# PAGE4_-_SENSORS.net
KiCad netlist of a schematic drawn in Altium Designer
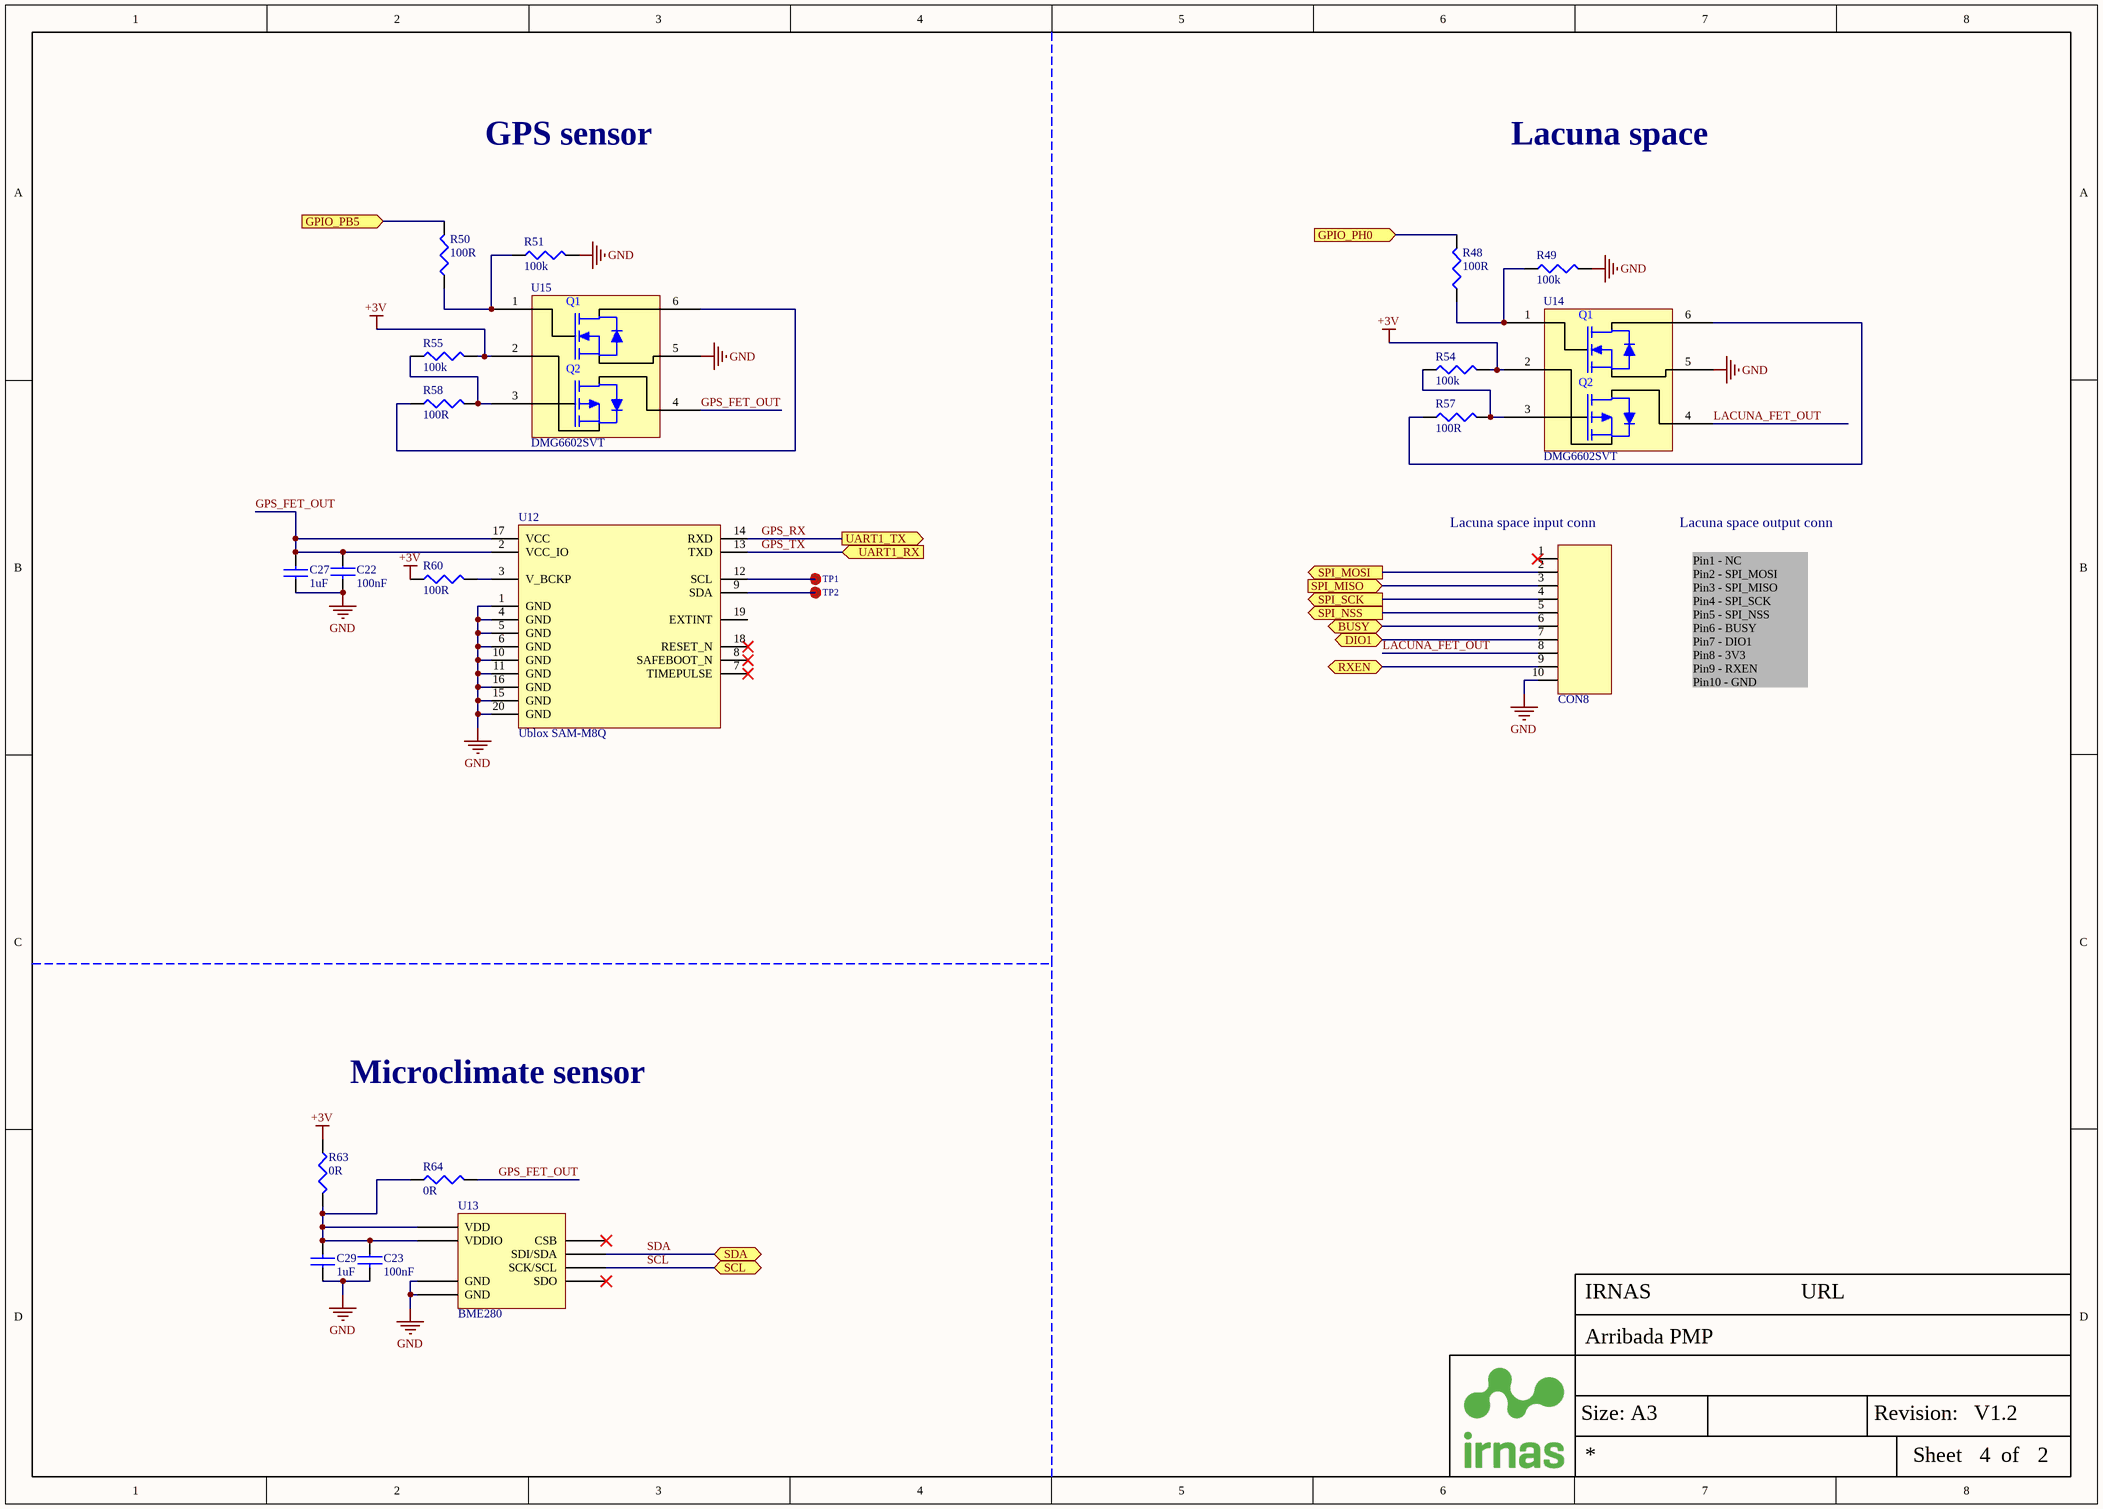
[diagram p0: PAGE4 - SENSORS.SchDoc]

(export (version "E")
  (design (tool "Eeschema 10.0.6"))
  (components
    (comp (ref "C22")
      (value "100nF")
      (footprint "CAP0603")
      (description "MURATA - GRM188R71C104KA01J - CAP, MLCC, X7R, 0.1UF, 16V, 0603")
      (fields
        (field (name "MANUFACTURER") "MURATA")
        (field (name "MANUFACTURER PART NUMBER") "GRM188R71C104KA01J")
      )
      (libsource (lib "Passive") (part "C - 100nF"))
    )
    (comp (ref "C23")
      (value "100nF")
      (footprint "CAP0603")
      (description "MURATA - GRM188R71C104KA01J - CAP, MLCC, X7R, 0.1UF, 16V, 0603")
      (fields
        (field (name "MANUFACTURER") "MURATA")
        (field (name "MANUFACTURER PART NUMBER") "GRM188R71C104KA01J")
      )
      (libsource (lib "Passive") (part "C - 100nF"))
    )
    (comp (ref "C27")
      (value "1uF")
      (footprint "CAP0603")
      (description "MURATA - GRM188R61H105KAALD - CAP, MLCC, X5R, 1UF, 50V, 0603")
      (fields
        (field (name "MANUFACTURER") "MURATA")
        (field (name "MANUFACTURER PART NUMBER") "GRM188R61H105KAALD")
      )
      (libsource (lib "Passive") (part "C - 1uF"))
    )
    (comp (ref "C29")
      (value "1uF")
      (footprint "CAP0603")
      (description "MURATA - GRM188R61H105KAALD - CAP, MLCC, X5R, 1UF, 50V, 0603")
      (fields
        (field (name "MANUFACTURER") "MURATA")
        (field (name "MANUFACTURER PART NUMBER") "GRM188R61H105KAALD")
      )
      (libsource (lib "Passive") (part "C - 1uF"))
    )
    (comp (ref "CON8")
      (value "53261-1071")
      (footprint "PICOBLADE 10PIN")
      (description "Wire-To-Board Connector, Right Angle, 1.25 mm, 10 Contacts, Header, PicoBlade 53261 Series")
      (libsource (lib "Connectors") (part "PicoBlade 10pin"))
    )
    (comp (ref "R48")
      (value "100R")
      (footprint "RES0603")
      (description "MULTICOMP - MC0063W06031100R - RES, THICK FILM, 100R, 1%, 0.063W, 0603")
      (fields
        (field (name "MANUFACTURER") "MULTICOMP")
        (field (name "MANUFACTURER PART NUMBER") "MC0063W06031100R")
      )
      (libsource (lib "Passive") (part "R - 100R"))
    )
    (comp (ref "R49")
      (value "100k")
      (footprint "RES0603")
      (description "MULTICOMP - MCMR06X104 JTL - RES, CERAMIC, 100K, 5%, 0.1W, 0603")
      (fields
        (field (name "MANUFACTURER") "MULTICOMP")
        (field (name "MANUFACTURER PART NUMBER") "MCMR06X104 JTL")
      )
      (libsource (lib "Passive") (part "R - 100k"))
    )
    (comp (ref "R50")
      (value "100R")
      (footprint "RES0603")
      (description "MULTICOMP - MC0063W06031100R - RES, THICK FILM, 100R, 1%, 0.063W, 0603")
      (fields
        (field (name "MANUFACTURER") "MULTICOMP")
        (field (name "MANUFACTURER PART NUMBER") "MC0063W06031100R")
      )
      (libsource (lib "Passive") (part "R - 100R"))
    )
    (comp (ref "R51")
      (value "100k")
      (footprint "RES0603")
      (description "MULTICOMP - MCMR06X104 JTL - RES, CERAMIC, 100K, 5%, 0.1W, 0603")
      (fields
        (field (name "MANUFACTURER") "MULTICOMP")
        (field (name "MANUFACTURER PART NUMBER") "MCMR06X104 JTL")
      )
      (libsource (lib "Passive") (part "R - 100k"))
    )
    (comp (ref "R54")
      (value "100k")
      (footprint "RES0603")
      (description "MULTICOMP - MCMR06X104 JTL - RES, CERAMIC, 100K, 5%, 0.1W, 0603")
      (fields
        (field (name "MANUFACTURER") "MULTICOMP")
        (field (name "MANUFACTURER PART NUMBER") "MCMR06X104 JTL")
      )
      (libsource (lib "Passive") (part "R - 100k"))
    )
    (comp (ref "R55")
      (value "100k")
      (footprint "RES0603")
      (description "MULTICOMP - MCMR06X104 JTL - RES, CERAMIC, 100K, 5%, 0.1W, 0603")
      (fields
        (field (name "MANUFACTURER") "MULTICOMP")
        (field (name "MANUFACTURER PART NUMBER") "MCMR06X104 JTL")
      )
      (libsource (lib "Passive") (part "R - 100k"))
    )
    (comp (ref "R57")
      (value "100R")
      (footprint "RES0603")
      (description "MULTICOMP - MC0063W06031100R - RES, THICK FILM, 100R, 1%, 0.063W, 0603")
      (fields
        (field (name "MANUFACTURER") "MULTICOMP")
        (field (name "MANUFACTURER PART NUMBER") "MC0063W06031100R")
      )
      (libsource (lib "Passive") (part "R - 100R"))
    )
    (comp (ref "R58")
      (value "100R")
      (footprint "RES0603")
      (description "MULTICOMP - MC0063W06031100R - RES, THICK FILM, 100R, 1%, 0.063W, 0603")
      (fields
        (field (name "MANUFACTURER") "MULTICOMP")
        (field (name "MANUFACTURER PART NUMBER") "MC0063W06031100R")
      )
      (libsource (lib "Passive") (part "R - 100R"))
    )
    (comp (ref "R60")
      (value "100R")
      (footprint "RES0603")
      (description "MULTICOMP - MC0063W06031100R - RES, THICK FILM, 100R, 1%, 0.063W, 0603")
      (fields
        (field (name "MANUFACTURER") "MULTICOMP")
        (field (name "MANUFACTURER PART NUMBER") "MC0063W06031100R")
      )
      (libsource (lib "Passive") (part "R - 100R"))
    )
    (comp (ref "R63")
      (value "0R")
      (footprint "RES0603")
      (description "BOURNS - CR0603-J/-000ELF - RES, THICK FILM, 0R, 5%, 0.1W, 0603")
      (fields
        (field (name "MANUFACTURER") "BOURNS")
        (field (name "MANUFACTURER PART NUMBER") "CR0603-J/-000ELF")
      )
      (libsource (lib "Passive") (part "R - 0R"))
    )
    (comp (ref "R64")
      (value "0R")
      (footprint "RES0603")
      (description "BOURNS - CR0603-J/-000ELF - RES, THICK FILM, 0R, 5%, 0.1W, 0603")
      (fields
        (field (name "MANUFACTURER") "BOURNS")
        (field (name "MANUFACTURER PART NUMBER") "CR0603-J/-000ELF")
      )
      (libsource (lib "Passive") (part "R - 0R"))
    )
    (comp (ref "TP1")
      (value "TestPoint")
      (footprint "Passive:TestPoint:1.2x1.2mm")
      (description "TEST POINT ROUND SMD")
      (libsource (lib "Passive") (part "TestPoint"))
    )
    (comp (ref "TP2")
      (value "TestPoint")
      (footprint "Passive:TestPoint:1.2x1.2mm")
      (description "TEST POINT ROUND SMD")
      (libsource (lib "Passive") (part "TestPoint"))
    )
    (comp (ref "U12")
      (value "Ublox SAM-M8Q")
      (footprint "SAM-M8Q")
      (description "SAM-M8 RF Receiver BeiDou, Galileo, GLONASS, GNSS, GPS -160dBm")
      (fields (field (name "MANUFACTURER") "u-blox") (field (name "MANUFACTURER PART NUMBER") "MAX-M8Q-0"))
      (libsource (lib "Active") (part "RF - UBLOX-SAM-M8Q"))
    )
    (comp (ref "U13")
      (value "BME280")
      (footprint "BME280")
      (description "Humidity Temperature Sensor 0 ~ 100% RH I²C, SPI ±3% 1s Surface Mount")
      (libsource (lib "Active") (part "SEN - BME280"))
    )
    (comp (ref "U14")
      (value "DMG6602SVT")
      (footprint "TSOT26")
      (description "Dual MOSFET, N and P Channel, 3.4 A, 30 V, 0.038 ohm, 10 V, 1 V")
      (libsource (lib "Active") (part "T_M - DMG6602SVT"))
    )
    (comp (ref "U15")
      (value "DMG6602SVT")
      (footprint "TSOT26")
      (description "Dual MOSFET, N and P Channel, 3.4 A, 30 V, 0.038 ohm, 10 V, 1 V")
      (libsource (lib "Active") (part "T_M - DMG6602SVT"))
    )
  )
  (nets
    (net (code "1") (name "+3V") (class "Default")
      (node (ref "R54") (pin "2") (pinfunction "2_2") (pintype "passive"))
      (node (ref "R55") (pin "2") (pinfunction "2_2") (pintype "passive"))
      (node (ref "R60") (pin "1") (pinfunction "1_1") (pintype "passive"))
      (node (ref "R63") (pin "1") (pinfunction "1_1") (pintype "passive"))
      (node (ref "U14") (pin "2") (pinfunction "S2_2") (pintype "open_collector"))
      (node (ref "U15") (pin "2") (pinfunction "S2_2") (pintype "open_collector"))
    )
    (net (code "2") (name "/BUSY") (class "Default")
      (node (ref "CON8") (pin "6") (pinfunction "6_6") (pintype "passive"))
    )
    (net (code "3") (name "/DIO1") (class "Default")
      (node (ref "CON8") (pin "7") (pinfunction "7_7") (pintype "passive"))
    )
    (net (code "4") (name "/GPIO_PB5") (class "Default")
      (node (ref "R50") (pin "2") (pinfunction "2_2") (pintype "passive"))
    )
    (net (code "5") (name "/GPIO_PH0") (class "Default")
      (node (ref "R48") (pin "2") (pinfunction "2_2") (pintype "passive"))
    )
    (net (code "6") (name "/GPS_FET_OUT") (class "Default")
      (node (ref "C22") (pin "1") (pinfunction "1_1") (pintype "passive"))
      (node (ref "C27") (pin "2") (pinfunction "2_2") (pintype "passive"))
      (node (ref "R64") (pin "2") (pinfunction "2_2") (pintype "passive"))
      (node (ref "U12") (pin "17") (pinfunction "VCC_17") (pintype "passive"))
      (node (ref "U12") (pin "2") (pinfunction "VCC_IO_2") (pintype "passive"))
      (node (ref "U15") (pin "4") (pinfunction "D2_4") (pintype "open_collector"))
    )
    (net (code "7") (name "/GPS_RX") (class "Default")
      (node (ref "U12") (pin "14") (pinfunction "RXD_14") (pintype "passive"))
    )
    (net (code "8") (name "/GPS_TX") (class "Default")
      (node (ref "U12") (pin "13") (pinfunction "TXD_13") (pintype "passive"))
    )
    (net (code "9") (name "/LACUNA_FET_OUT") (class "Default")
      (node (ref "CON8") (pin "8") (pinfunction "8_8") (pintype "passive"))
      (node (ref "U14") (pin "4") (pinfunction "D2_4") (pintype "open_collector"))
    )
    (net (code "10") (name "/RXEN") (class "Default")
      (node (ref "CON8") (pin "9") (pinfunction "9_9") (pintype "passive"))
    )
    (net (code "11") (name "/SCL") (class "Default")
      (node (ref "U13") (pin "4") (pinfunction "SCK/SCL_4") (pintype "passive"))
    )
    (net (code "12") (name "/SDA") (class "Default")
      (node (ref "U13") (pin "3") (pinfunction "SDI/SDA_3") (pintype "passive"))
    )
    (net (code "13") (name "/SPI_MISO") (class "Default")
      (node (ref "CON8") (pin "3") (pinfunction "3_3") (pintype "passive"))
    )
    (net (code "14") (name "/SPI_MOSI") (class "Default")
      (node (ref "CON8") (pin "2") (pinfunction "2_2") (pintype "passive"))
    )
    (net (code "15") (name "/SPI_NSS") (class "Default")
      (node (ref "CON8") (pin "5") (pinfunction "5_5") (pintype "passive"))
    )
    (net (code "16") (name "/SPI_SCK") (class "Default")
      (node (ref "CON8") (pin "4") (pinfunction "4_4") (pintype "passive"))
    )
    (net (code "17") (name "GND") (class "Default")
      (node (ref "C22") (pin "2") (pinfunction "2_2") (pintype "passive"))
      (node (ref "C23") (pin "2") (pinfunction "2_2") (pintype "passive"))
      (node (ref "C27") (pin "1") (pinfunction "1_1") (pintype "passive"))
      (node (ref "C29") (pin "1") (pinfunction "1_1") (pintype "passive"))
      (node (ref "CON8") (pin "10") (pinfunction "10_10") (pintype "passive"))
      (node (ref "R49") (pin "2") (pinfunction "2_2") (pintype "passive"))
      (node (ref "R51") (pin "2") (pinfunction "2_2") (pintype "passive"))
      (node (ref "U12") (pin "1") (pinfunction "GND_1") (pintype "passive"))
      (node (ref "U12") (pin "10") (pinfunction "GND_10") (pintype "passive"))
      (node (ref "U12") (pin "11") (pinfunction "GND_11") (pintype "passive"))
      (node (ref "U12") (pin "15") (pinfunction "GND_15") (pintype "passive"))
      (node (ref "U12") (pin "16") (pinfunction "GND_16") (pintype "passive"))
      (node (ref "U12") (pin "20") (pinfunction "GND_20") (pintype "passive"))
      (node (ref "U12") (pin "4") (pinfunction "GND_4") (pintype "passive"))
      (node (ref "U12") (pin "5") (pinfunction "GND_5") (pintype "passive"))
      (node (ref "U12") (pin "6") (pinfunction "GND_6") (pintype "passive"))
      (node (ref "U13") (pin "1") (pinfunction "GND_1") (pintype "passive"))
      (node (ref "U13") (pin "7") (pinfunction "GND_7") (pintype "passive"))
      (node (ref "U14") (pin "5") (pinfunction "S1_5") (pintype "open_collector"))
      (node (ref "U15") (pin "5") (pinfunction "S1_5") (pintype "open_collector"))
    )
    (net (code "18") (name "Net-(U12-SCL)") (class "Default")
      (node (ref "TP1") (pin "0") (pinfunction "0_0") (pintype "passive"))
      (node (ref "U12") (pin "12") (pinfunction "SCL_12") (pintype "passive"))
    )
    (net (code "19") (name "Net-(U12-SDA)") (class "Default")
      (node (ref "TP2") (pin "0") (pinfunction "0_0") (pintype "passive"))
      (node (ref "U12") (pin "9") (pinfunction "SDA_9") (pintype "passive"))
    )
    (net (code "20") (name "Net-(U12-V_BCKP)") (class "Default")
      (node (ref "R60") (pin "2") (pinfunction "2_2") (pintype "passive"))
      (node (ref "U12") (pin "3") (pinfunction "V_BCKP_3") (pintype "passive"))
    )
    (net (code "21") (name "Net-(U13-VDD)") (class "Default")
      (node (ref "C23") (pin "1") (pinfunction "1_1") (pintype "passive"))
      (node (ref "C29") (pin "2") (pinfunction "2_2") (pintype "passive"))
      (node (ref "R63") (pin "2") (pinfunction "2_2") (pintype "passive"))
      (node (ref "R64") (pin "1") (pinfunction "1_1") (pintype "passive"))
      (node (ref "U13") (pin "6") (pinfunction "VDDIO_6") (pintype "passive"))
      (node (ref "U13") (pin "8") (pinfunction "VDD_8") (pintype "passive"))
    )
    (net (code "22") (name "Net-(U14-D1)") (class "Default")
      (node (ref "R57") (pin "1") (pinfunction "1_1") (pintype "passive"))
      (node (ref "U14") (pin "6") (pinfunction "D1_6") (pintype "open_collector"))
    )
    (net (code "23") (name "Net-(U14-G1)") (class "Default")
      (node (ref "R48") (pin "1") (pinfunction "1_1") (pintype "passive"))
      (node (ref "R49") (pin "1") (pinfunction "1_1") (pintype "passive"))
      (node (ref "U14") (pin "1") (pinfunction "G1_1") (pintype "open_collector"))
    )
    (net (code "24") (name "Net-(U14-G2)") (class "Default")
      (node (ref "R54") (pin "1") (pinfunction "1_1") (pintype "passive"))
      (node (ref "R57") (pin "2") (pinfunction "2_2") (pintype "passive"))
      (node (ref "U14") (pin "3") (pinfunction "G2_3") (pintype "open_collector"))
    )
    (net (code "25") (name "Net-(U15-D1)") (class "Default")
      (node (ref "R58") (pin "1") (pinfunction "1_1") (pintype "passive"))
      (node (ref "U15") (pin "6") (pinfunction "D1_6") (pintype "open_collector"))
    )
    (net (code "26") (name "Net-(U15-G1)") (class "Default")
      (node (ref "R50") (pin "1") (pinfunction "1_1") (pintype "passive"))
      (node (ref "R51") (pin "1") (pinfunction "1_1") (pintype "passive"))
      (node (ref "U15") (pin "1") (pinfunction "G1_1") (pintype "open_collector"))
    )
    (net (code "27") (name "Net-(U15-G2)") (class "Default")
      (node (ref "R55") (pin "1") (pinfunction "1_1") (pintype "passive"))
      (node (ref "R58") (pin "2") (pinfunction "2_2") (pintype "passive"))
      (node (ref "U15") (pin "3") (pinfunction "G2_3") (pintype "open_collector"))
    )
    (net (code "28") (name "unconnected-(CON8-Pad1)") (class "Default")
      (node (ref "CON8") (pin "1") (pinfunction "1_1") (pintype "passive+no_connect"))
    )
    (net (code "29") (name "unconnected-(U12-EXTINT-Pad19)") (class "Default")
      (node (ref "U12") (pin "19") (pinfunction "EXTINT_19") (pintype "passive"))
    )
    (net (code "30") (name "unconnected-(U12-RESET_N-Pad18)") (class "Default")
      (node (ref "U12") (pin "18") (pinfunction "RESET_N_18") (pintype "passive+no_connect"))
    )
    (net (code "31") (name "unconnected-(U12-SAFEBOOT_N-Pad8)") (class "Default")
      (node (ref "U12") (pin "8") (pinfunction "SAFEBOOT_N_8") (pintype "passive+no_connect"))
    )
    (net (code "32") (name "unconnected-(U12-TIMEPULSE-Pad7)") (class "Default")
      (node (ref "U12") (pin "7") (pinfunction "TIMEPULSE_7") (pintype "passive+no_connect"))
    )
    (net (code "33") (name "unconnected-(U13-CSB-Pad2)") (class "Default")
      (node (ref "U13") (pin "2") (pinfunction "CSB_2") (pintype "passive+no_connect"))
    )
    (net (code "34") (name "unconnected-(U13-SDO-Pad5)") (class "Default")
      (node (ref "U13") (pin "5") (pinfunction "SDO_5") (pintype "passive+no_connect"))
    )
  )
)
